# Prototype1.net
KiCad netlist of a schematic drawn in EAGLE
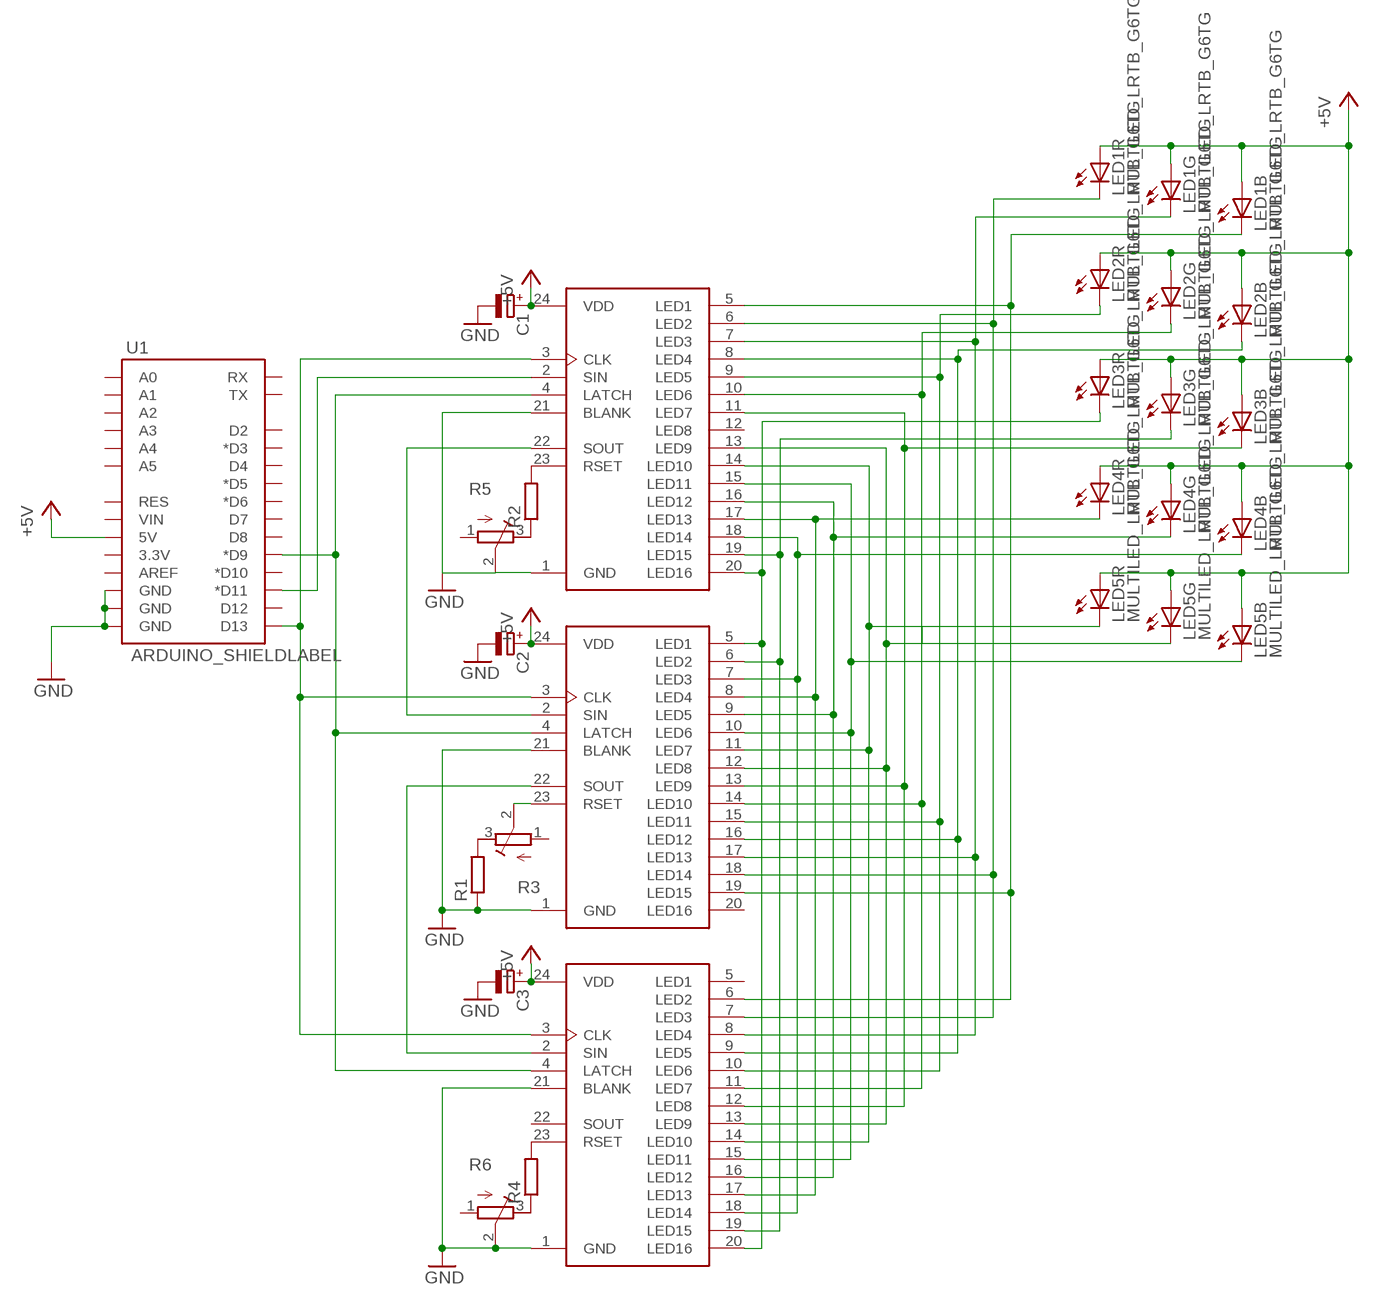
[diagram p0: schematic, sheet 1]

(export (version "E")
  (design (tool "Eeschema 10.0.6"))
  (components
    (comp (ref "C1")
      (value "CPOL-EUA/3216-18W")
      (footprint "eagle-import:A_3216-18W")
      (libsource (lib "eagle-import") (part "CPOL-EUA/3216-18W"))
    )
    (comp (ref "C2")
      (value "CPOL-EUA/3216-18W")
      (footprint "eagle-import:A_3216-18W")
      (libsource (lib "eagle-import") (part "CPOL-EUA/3216-18W"))
    )
    (comp (ref "C3")
      (value "CPOL-EUA/3216-18W")
      (footprint "eagle-import:A_3216-18W")
      (libsource (lib "eagle-import") (part "CPOL-EUA/3216-18W"))
    )
    (comp (ref "LED1")
      (value "MULTILED_LRTB_G6TG")
      (footprint "eagle-import:P-LCC-6_TOPLED")
      (libsource (lib "eagle-import") (part "MULTILED_LRTB_G6TG"))
    )
    (comp (ref "LED2")
      (value "MULTILED_LRTB_G6TG")
      (footprint "eagle-import:P-LCC-6_TOPLED")
      (libsource (lib "eagle-import") (part "MULTILED_LRTB_G6TG"))
    )
    (comp (ref "LED3")
      (value "MULTILED_LRTB_G6TG")
      (footprint "eagle-import:P-LCC-6_TOPLED")
      (libsource (lib "eagle-import") (part "MULTILED_LRTB_G6TG"))
    )
    (comp (ref "LED4")
      (value "MULTILED_LRTB_G6TG")
      (footprint "eagle-import:P-LCC-6_TOPLED")
      (libsource (lib "eagle-import") (part "MULTILED_LRTB_G6TG"))
    )
    (comp (ref "LED5")
      (value "MULTILED_LRTB_G6TG")
      (footprint "eagle-import:P-LCC-6_TOPLED")
      (libsource (lib "eagle-import") (part "MULTILED_LRTB_G6TG"))
    )
    (comp (ref "R1")
      (value "R-EU_0204/7")
      (footprint "eagle-import:0204_7")
      (libsource (lib "eagle-import") (part "R-EU_0204/7"))
    )
    (comp (ref "R2")
      (value "R-EU_0204/7")
      (footprint "eagle-import:0204_7")
      (libsource (lib "eagle-import") (part "R-EU_0204/7"))
    )
    (comp (ref "R3")
      (value "R-TRIMM3165W")
      (footprint "eagle-import:RTRIM3165W")
      (libsource (lib "eagle-import") (part "R-TRIMM3165W"))
    )
    (comp (ref "R4")
      (value "R-EU_0204/7")
      (footprint "eagle-import:0204_7")
      (libsource (lib "eagle-import") (part "R-EU_0204/7"))
    )
    (comp (ref "R5")
      (value "R-TRIMM3165W")
      (footprint "eagle-import:RTRIM3165W")
      (libsource (lib "eagle-import") (part "R-TRIMM3165W"))
    )
    (comp (ref "R6")
      (value "R-TRIMM3165W")
      (footprint "eagle-import:RTRIM3165W")
      (libsource (lib "eagle-import") (part "R-TRIMM3165W"))
    )
    (comp (ref "U$1")
      (value "CAT4016")
      (footprint "eagle-import:SOIC24W")
      (libsource (lib "eagle-import") (part "CAT4016"))
    )
    (comp (ref "U$2")
      (value "CAT4016")
      (footprint "eagle-import:SOIC24W")
      (libsource (lib "eagle-import") (part "CAT4016"))
    )
    (comp (ref "U$3")
      (value "CAT4016")
      (footprint "eagle-import:SOIC24W")
      (libsource (lib "eagle-import") (part "CAT4016"))
    )
    (comp (ref "U1")
      (value "ARDUINO_SHIELDLABEL")
      (footprint "eagle-import:DUEMILANOVE_SHIELD")
      (libsource (lib "eagle-import") (part "ARDUINO_SHIELDLABEL"))
    )
  )
  (nets
    (net (code "1") (name "+5V") (class "Default")
      (node (ref "C1") (pin "+") (pinfunction "+_+") (pintype "passive"))
      (node (ref "C2") (pin "+") (pinfunction "+_+") (pintype "passive"))
      (node (ref "C3") (pin "+") (pinfunction "+_+") (pintype "passive"))
      (node (ref "LED1") (pin "A1") (pinfunction "A_A1") (pintype "passive"))
      (node (ref "LED1") (pin "A2") (pinfunction "A_A2") (pintype "passive"))
      (node (ref "LED1") (pin "A3") (pinfunction "A_A3") (pintype "passive"))
      (node (ref "LED2") (pin "A1") (pinfunction "A_A1") (pintype "passive"))
      (node (ref "LED2") (pin "A2") (pinfunction "A_A2") (pintype "passive"))
      (node (ref "LED2") (pin "A3") (pinfunction "A_A3") (pintype "passive"))
      (node (ref "LED3") (pin "A1") (pinfunction "A_A1") (pintype "passive"))
      (node (ref "LED3") (pin "A2") (pinfunction "A_A2") (pintype "passive"))
      (node (ref "LED3") (pin "A3") (pinfunction "A_A3") (pintype "passive"))
      (node (ref "LED4") (pin "A1") (pinfunction "A_A1") (pintype "passive"))
      (node (ref "LED4") (pin "A2") (pinfunction "A_A2") (pintype "passive"))
      (node (ref "LED4") (pin "A3") (pinfunction "A_A3") (pintype "passive"))
      (node (ref "LED5") (pin "A1") (pinfunction "A_A1") (pintype "passive"))
      (node (ref "LED5") (pin "A2") (pinfunction "A_A2") (pintype "passive"))
      (node (ref "LED5") (pin "A3") (pinfunction "A_A3") (pintype "passive"))
      (node (ref "U$1") (pin "24") (pinfunction "VDD_24") (pintype "bidirectional"))
      (node (ref "U$2") (pin "24") (pinfunction "VDD_24") (pintype "bidirectional"))
      (node (ref "U$3") (pin "24") (pinfunction "VDD_24") (pintype "bidirectional"))
      (node (ref "U1") (pin "5V") (pinfunction "5V_5V") (pintype "bidirectional"))
    )
    (net (code "2") (name "GND") (class "Default")
      (node (ref "C1") (pin "-") (pinfunction "-_-") (pintype "passive"))
      (node (ref "C2") (pin "-") (pinfunction "-_-") (pintype "passive"))
      (node (ref "C3") (pin "-") (pinfunction "-_-") (pintype "passive"))
      (node (ref "R1") (pin "1") (pinfunction "1_1") (pintype "passive"))
      (node (ref "R5") (pin "2") (pinfunction "S_2") (pintype "passive"))
      (node (ref "R6") (pin "2") (pinfunction "S_2") (pintype "passive"))
      (node (ref "U$1") (pin "1") (pinfunction "GND_1") (pintype "bidirectional"))
      (node (ref "U$1") (pin "21") (pinfunction "BLANK_21") (pintype "bidirectional"))
      (node (ref "U$2") (pin "1") (pinfunction "GND_1") (pintype "bidirectional"))
      (node (ref "U$2") (pin "21") (pinfunction "BLANK_21") (pintype "bidirectional"))
      (node (ref "U$3") (pin "1") (pinfunction "GND_1") (pintype "bidirectional"))
      (node (ref "U$3") (pin "21") (pinfunction "BLANK_21") (pintype "bidirectional"))
      (node (ref "U1") (pin "GND@0") (pinfunction "GND_GND@0") (pintype "bidirectional"))
      (node (ref "U1") (pin "GND@1") (pinfunction "GND_GND@1") (pintype "bidirectional"))
      (node (ref "U1") (pin "GND@2") (pinfunction "GND_GND@2") (pintype "bidirectional"))
    )
    (net (code "3") (name "Net-(LED1A-C)") (class "Default")
      (node (ref "LED1") (pin "C3") (pinfunction "C_C3") (pintype "passive"))
      (node (ref "U$1") (pin "19") (pinfunction "LED15_19") (pintype "bidirectional"))
      (node (ref "U$2") (pin "6") (pinfunction "LED2_6") (pintype "bidirectional"))
      (node (ref "U$3") (pin "5") (pinfunction "LED1_5") (pintype "bidirectional"))
    )
    (net (code "4") (name "Net-(LED1B-C)") (class "Default")
      (node (ref "LED1") (pin "C2") (pinfunction "C_C2") (pintype "passive"))
      (node (ref "U$1") (pin "17") (pinfunction "LED13_17") (pintype "bidirectional"))
      (node (ref "U$2") (pin "8") (pinfunction "LED4_8") (pintype "bidirectional"))
      (node (ref "U$3") (pin "7") (pinfunction "LED3_7") (pintype "bidirectional"))
    )
    (net (code "5") (name "Net-(LED1C-C)") (class "Default")
      (node (ref "LED1") (pin "C1") (pinfunction "C_C1") (pintype "passive"))
      (node (ref "U$1") (pin "18") (pinfunction "LED14_18") (pintype "bidirectional"))
      (node (ref "U$2") (pin "7") (pinfunction "LED3_7") (pintype "bidirectional"))
      (node (ref "U$3") (pin "6") (pinfunction "LED2_6") (pintype "bidirectional"))
    )
    (net (code "6") (name "Net-(LED2A-C)") (class "Default")
      (node (ref "LED2") (pin "C3") (pinfunction "C_C3") (pintype "passive"))
      (node (ref "U$1") (pin "16") (pinfunction "LED12_16") (pintype "bidirectional"))
      (node (ref "U$2") (pin "9") (pinfunction "LED5_9") (pintype "bidirectional"))
      (node (ref "U$3") (pin "8") (pinfunction "LED4_8") (pintype "bidirectional"))
    )
    (net (code "7") (name "Net-(LED2B-C)") (class "Default")
      (node (ref "LED2") (pin "C2") (pinfunction "C_C2") (pintype "passive"))
      (node (ref "U$1") (pin "14") (pinfunction "LED10_14") (pintype "bidirectional"))
      (node (ref "U$2") (pin "11") (pinfunction "LED7_11") (pintype "bidirectional"))
      (node (ref "U$3") (pin "10") (pinfunction "LED6_10") (pintype "bidirectional"))
    )
    (net (code "8") (name "Net-(LED2C-C)") (class "Default")
      (node (ref "LED2") (pin "C1") (pinfunction "C_C1") (pintype "passive"))
      (node (ref "U$1") (pin "15") (pinfunction "LED11_15") (pintype "bidirectional"))
      (node (ref "U$2") (pin "10") (pinfunction "LED6_10") (pintype "bidirectional"))
      (node (ref "U$3") (pin "9") (pinfunction "LED5_9") (pintype "bidirectional"))
    )
    (net (code "9") (name "Net-(LED3A-C)") (class "Default")
      (node (ref "LED3") (pin "C3") (pinfunction "C_C3") (pintype "passive"))
      (node (ref "U$1") (pin "13") (pinfunction "LED9_13") (pintype "bidirectional"))
      (node (ref "U$2") (pin "12") (pinfunction "LED8_12") (pintype "bidirectional"))
      (node (ref "U$3") (pin "11") (pinfunction "LED7_11") (pintype "bidirectional"))
    )
    (net (code "10") (name "Net-(LED3B-C)") (class "Default")
      (node (ref "LED3") (pin "C2") (pinfunction "C_C2") (pintype "passive"))
      (node (ref "U$1") (pin "6") (pinfunction "LED2_6") (pintype "bidirectional"))
      (node (ref "U$2") (pin "19") (pinfunction "LED15_19") (pintype "bidirectional"))
      (node (ref "U$3") (pin "19") (pinfunction "LED15_19") (pintype "bidirectional"))
    )
    (net (code "11") (name "Net-(LED3C-C)") (class "Default")
      (node (ref "LED3") (pin "C1") (pinfunction "C_C1") (pintype "passive"))
      (node (ref "U$1") (pin "5") (pinfunction "LED1_5") (pintype "bidirectional"))
      (node (ref "U$2") (pin "20") (pinfunction "LED16_20") (pintype "bidirectional"))
      (node (ref "U$3") (pin "20") (pinfunction "LED16_20") (pintype "bidirectional"))
    )
    (net (code "12") (name "Net-(LED4A-C)") (class "Default")
      (node (ref "LED4") (pin "C3") (pinfunction "C_C3") (pintype "passive"))
      (node (ref "U$1") (pin "7") (pinfunction "LED3_7") (pintype "bidirectional"))
      (node (ref "U$2") (pin "18") (pinfunction "LED14_18") (pintype "bidirectional"))
      (node (ref "U$3") (pin "18") (pinfunction "LED14_18") (pintype "bidirectional"))
    )
    (net (code "13") (name "Net-(LED4B-C)") (class "Default")
      (node (ref "LED4") (pin "C2") (pinfunction "C_C2") (pintype "passive"))
      (node (ref "U$1") (pin "9") (pinfunction "LED5_9") (pintype "bidirectional"))
      (node (ref "U$2") (pin "16") (pinfunction "LED12_16") (pintype "bidirectional"))
      (node (ref "U$3") (pin "16") (pinfunction "LED12_16") (pintype "bidirectional"))
    )
    (net (code "14") (name "Net-(LED4C-C)") (class "Default")
      (node (ref "LED4") (pin "C1") (pinfunction "C_C1") (pintype "passive"))
      (node (ref "U$1") (pin "8") (pinfunction "LED4_8") (pintype "bidirectional"))
      (node (ref "U$2") (pin "17") (pinfunction "LED13_17") (pintype "bidirectional"))
      (node (ref "U$3") (pin "17") (pinfunction "LED13_17") (pintype "bidirectional"))
    )
    (net (code "15") (name "Net-(LED5A-C)") (class "Default")
      (node (ref "LED5") (pin "C3") (pinfunction "C_C3") (pintype "passive"))
      (node (ref "U$1") (pin "10") (pinfunction "LED6_10") (pintype "bidirectional"))
      (node (ref "U$2") (pin "15") (pinfunction "LED11_15") (pintype "bidirectional"))
      (node (ref "U$3") (pin "15") (pinfunction "LED11_15") (pintype "bidirectional"))
    )
    (net (code "16") (name "Net-(LED5B-C)") (class "Default")
      (node (ref "LED5") (pin "C2") (pinfunction "C_C2") (pintype "passive"))
      (node (ref "U$1") (pin "12") (pinfunction "LED8_12") (pintype "bidirectional"))
      (node (ref "U$2") (pin "13") (pinfunction "LED9_13") (pintype "bidirectional"))
      (node (ref "U$3") (pin "13") (pinfunction "LED9_13") (pintype "bidirectional"))
    )
    (net (code "17") (name "Net-(LED5C-C)") (class "Default")
      (node (ref "LED5") (pin "C1") (pinfunction "C_C1") (pintype "passive"))
      (node (ref "U$1") (pin "11") (pinfunction "LED7_11") (pintype "bidirectional"))
      (node (ref "U$2") (pin "14") (pinfunction "LED10_14") (pintype "bidirectional"))
      (node (ref "U$3") (pin "14") (pinfunction "LED10_14") (pintype "bidirectional"))
    )
    (net (code "18") (name "Net-(R3-E)") (class "Default")
      (node (ref "R1") (pin "2") (pinfunction "2_2") (pintype "passive"))
      (node (ref "R3") (pin "3") (pinfunction "E_3") (pintype "passive"))
    )
    (net (code "19") (name "Net-(R3-S)") (class "Default")
      (node (ref "R3") (pin "2") (pinfunction "S_2") (pintype "passive"))
      (node (ref "U$1") (pin "23") (pinfunction "RSET_23") (pintype "bidirectional"))
    )
    (net (code "20") (name "Net-(R5-E)") (class "Default")
      (node (ref "R2") (pin "1") (pinfunction "1_1") (pintype "passive"))
      (node (ref "R5") (pin "3") (pinfunction "E_3") (pintype "passive"))
    )
    (net (code "21") (name "Net-(R6-E)") (class "Default")
      (node (ref "R4") (pin "1") (pinfunction "1_1") (pintype "passive"))
      (node (ref "R6") (pin "3") (pinfunction "E_3") (pintype "passive"))
    )
    (net (code "22") (name "Net-(U$1-CLK)") (class "Default")
      (node (ref "U$1") (pin "3") (pinfunction "CLK_3") (pintype "bidirectional"))
      (node (ref "U$2") (pin "3") (pinfunction "CLK_3") (pintype "bidirectional"))
      (node (ref "U$3") (pin "3") (pinfunction "CLK_3") (pintype "bidirectional"))
      (node (ref "U1") (pin "D13") (pinfunction "D13_D13") (pintype "bidirectional"))
    )
    (net (code "23") (name "Net-(U$1-LATCH)") (class "Default")
      (node (ref "U$1") (pin "4") (pinfunction "LATCH_4") (pintype "bidirectional"))
      (node (ref "U$2") (pin "4") (pinfunction "LATCH_4") (pintype "bidirectional"))
      (node (ref "U$3") (pin "4") (pinfunction "LATCH_4") (pintype "bidirectional"))
      (node (ref "U1") (pin "D9") (pinfunction "*D9_D9") (pintype "bidirectional"))
    )
    (net (code "24") (name "Net-(U$1-SIN)") (class "Default")
      (node (ref "U$1") (pin "2") (pinfunction "SIN_2") (pintype "bidirectional"))
      (node (ref "U$3") (pin "22") (pinfunction "SOUT_22") (pintype "bidirectional"))
    )
    (net (code "25") (name "Net-(U$1-SOUT)") (class "Default")
      (node (ref "U$1") (pin "22") (pinfunction "SOUT_22") (pintype "bidirectional"))
      (node (ref "U$2") (pin "2") (pinfunction "SIN_2") (pintype "bidirectional"))
    )
    (net (code "26") (name "Net-(U$2-RSET)") (class "Default")
      (node (ref "R4") (pin "2") (pinfunction "2_2") (pintype "passive"))
      (node (ref "U$2") (pin "23") (pinfunction "RSET_23") (pintype "bidirectional"))
    )
    (net (code "27") (name "Net-(U$3-RSET)") (class "Default")
      (node (ref "R2") (pin "2") (pinfunction "2_2") (pintype "passive"))
      (node (ref "U$3") (pin "23") (pinfunction "RSET_23") (pintype "bidirectional"))
    )
    (net (code "28") (name "Net-(U$3-SIN)") (class "Default")
      (node (ref "U$3") (pin "2") (pinfunction "SIN_2") (pintype "bidirectional"))
      (node (ref "U1") (pin "D11") (pinfunction "*D11_D11") (pintype "bidirectional"))
    )
    (net (code "29") (name "unconnected-(R3-A-Pad1)") (class "Default")
      (node (ref "R3") (pin "1") (pinfunction "A_1") (pintype "passive"))
    )
    (net (code "30") (name "unconnected-(R5-A-Pad1)") (class "Default")
      (node (ref "R5") (pin "1") (pinfunction "A_1") (pintype "passive"))
    )
    (net (code "31") (name "unconnected-(R6-A-Pad1)") (class "Default")
      (node (ref "R6") (pin "1") (pinfunction "A_1") (pintype "passive"))
    )
    (net (code "32") (name "unconnected-(U$1-LED16-Pad20)") (class "Default")
      (node (ref "U$1") (pin "20") (pinfunction "LED16_20") (pintype "bidirectional"))
    )
    (net (code "33") (name "unconnected-(U$2-LED1-Pad5)") (class "Default")
      (node (ref "U$2") (pin "5") (pinfunction "LED1_5") (pintype "bidirectional"))
    )
    (net (code "34") (name "unconnected-(U$2-SOUT-Pad22)") (class "Default")
      (node (ref "U$2") (pin "22") (pinfunction "SOUT_22") (pintype "bidirectional"))
    )
    (net (code "35") (name "unconnected-(U$3-LED8-Pad12)") (class "Default")
      (node (ref "U$3") (pin "12") (pinfunction "LED8_12") (pintype "bidirectional"))
    )
    (net (code "36") (name "unconnected-(U1-*D3-PadD3)") (class "Default")
      (node (ref "U1") (pin "D3") (pinfunction "*D3_D3") (pintype "bidirectional"))
    )
    (net (code "37") (name "unconnected-(U1-*D5-PadD5)") (class "Default")
      (node (ref "U1") (pin "D5") (pinfunction "*D5_D5") (pintype "bidirectional"))
    )
    (net (code "38") (name "unconnected-(U1-*D6-PadD6)") (class "Default")
      (node (ref "U1") (pin "D6") (pinfunction "*D6_D6") (pintype "bidirectional"))
    )
    (net (code "39") (name "unconnected-(U1-*D10-PadD10)") (class "Default")
      (node (ref "U1") (pin "D10") (pinfunction "*D10_D10") (pintype "bidirectional"))
    )
    (net (code "40") (name "unconnected-(U1-Pad3.3V)") (class "Default")
      (node (ref "U1") (pin "3.3V") (pinfunction "3.3V_3.3V") (pintype "bidirectional"))
    )
    (net (code "41") (name "unconnected-(U1-PadA0)") (class "Default")
      (node (ref "U1") (pin "A0") (pinfunction "A0_A0") (pintype "bidirectional"))
    )
    (net (code "42") (name "unconnected-(U1-PadA1)") (class "Default")
      (node (ref "U1") (pin "A1") (pinfunction "A1_A1") (pintype "bidirectional"))
    )
    (net (code "43") (name "unconnected-(U1-PadA2)") (class "Default")
      (node (ref "U1") (pin "A2") (pinfunction "A2_A2") (pintype "bidirectional"))
    )
    (net (code "44") (name "unconnected-(U1-PadA3)") (class "Default")
      (node (ref "U1") (pin "A3") (pinfunction "A3_A3") (pintype "bidirectional"))
    )
    (net (code "45") (name "unconnected-(U1-PadA4)") (class "Default")
      (node (ref "U1") (pin "A4") (pinfunction "A4_A4") (pintype "bidirectional"))
    )
    (net (code "46") (name "unconnected-(U1-PadA5)") (class "Default")
      (node (ref "U1") (pin "A5") (pinfunction "A5_A5") (pintype "bidirectional"))
    )
    (net (code "47") (name "unconnected-(U1-PadAREF)") (class "Default")
      (node (ref "U1") (pin "AREF") (pinfunction "AREF_AREF") (pintype "bidirectional"))
    )
    (net (code "48") (name "unconnected-(U1-PadD2)") (class "Default")
      (node (ref "U1") (pin "D2") (pinfunction "D2_D2") (pintype "bidirectional"))
    )
    (net (code "49") (name "unconnected-(U1-PadD4)") (class "Default")
      (node (ref "U1") (pin "D4") (pinfunction "D4_D4") (pintype "bidirectional"))
    )
    (net (code "50") (name "unconnected-(U1-PadD7)") (class "Default")
      (node (ref "U1") (pin "D7") (pinfunction "D7_D7") (pintype "bidirectional"))
    )
    (net (code "51") (name "unconnected-(U1-PadD8)") (class "Default")
      (node (ref "U1") (pin "D8") (pinfunction "D8_D8") (pintype "bidirectional"))
    )
    (net (code "52") (name "unconnected-(U1-PadD12)") (class "Default")
      (node (ref "U1") (pin "D12") (pinfunction "D12_D12") (pintype "bidirectional"))
    )
    (net (code "53") (name "unconnected-(U1-PadRES)") (class "Default")
      (node (ref "U1") (pin "RES") (pinfunction "RES_RES") (pintype "bidirectional"))
    )
    (net (code "54") (name "unconnected-(U1-PadRX)") (class "Default")
      (node (ref "U1") (pin "RX") (pinfunction "RX_RX") (pintype "bidirectional"))
    )
    (net (code "55") (name "unconnected-(U1-PadTX)") (class "Default")
      (node (ref "U1") (pin "TX") (pinfunction "TX_TX") (pintype "bidirectional"))
    )
    (net (code "56") (name "unconnected-(U1-PadVIN)") (class "Default")
      (node (ref "U1") (pin "VIN") (pinfunction "VIN_VIN") (pintype "bidirectional"))
    )
  )
)
